# KeyboardInstrument.net
KiCad netlist of a schematic drawn in EAGLE
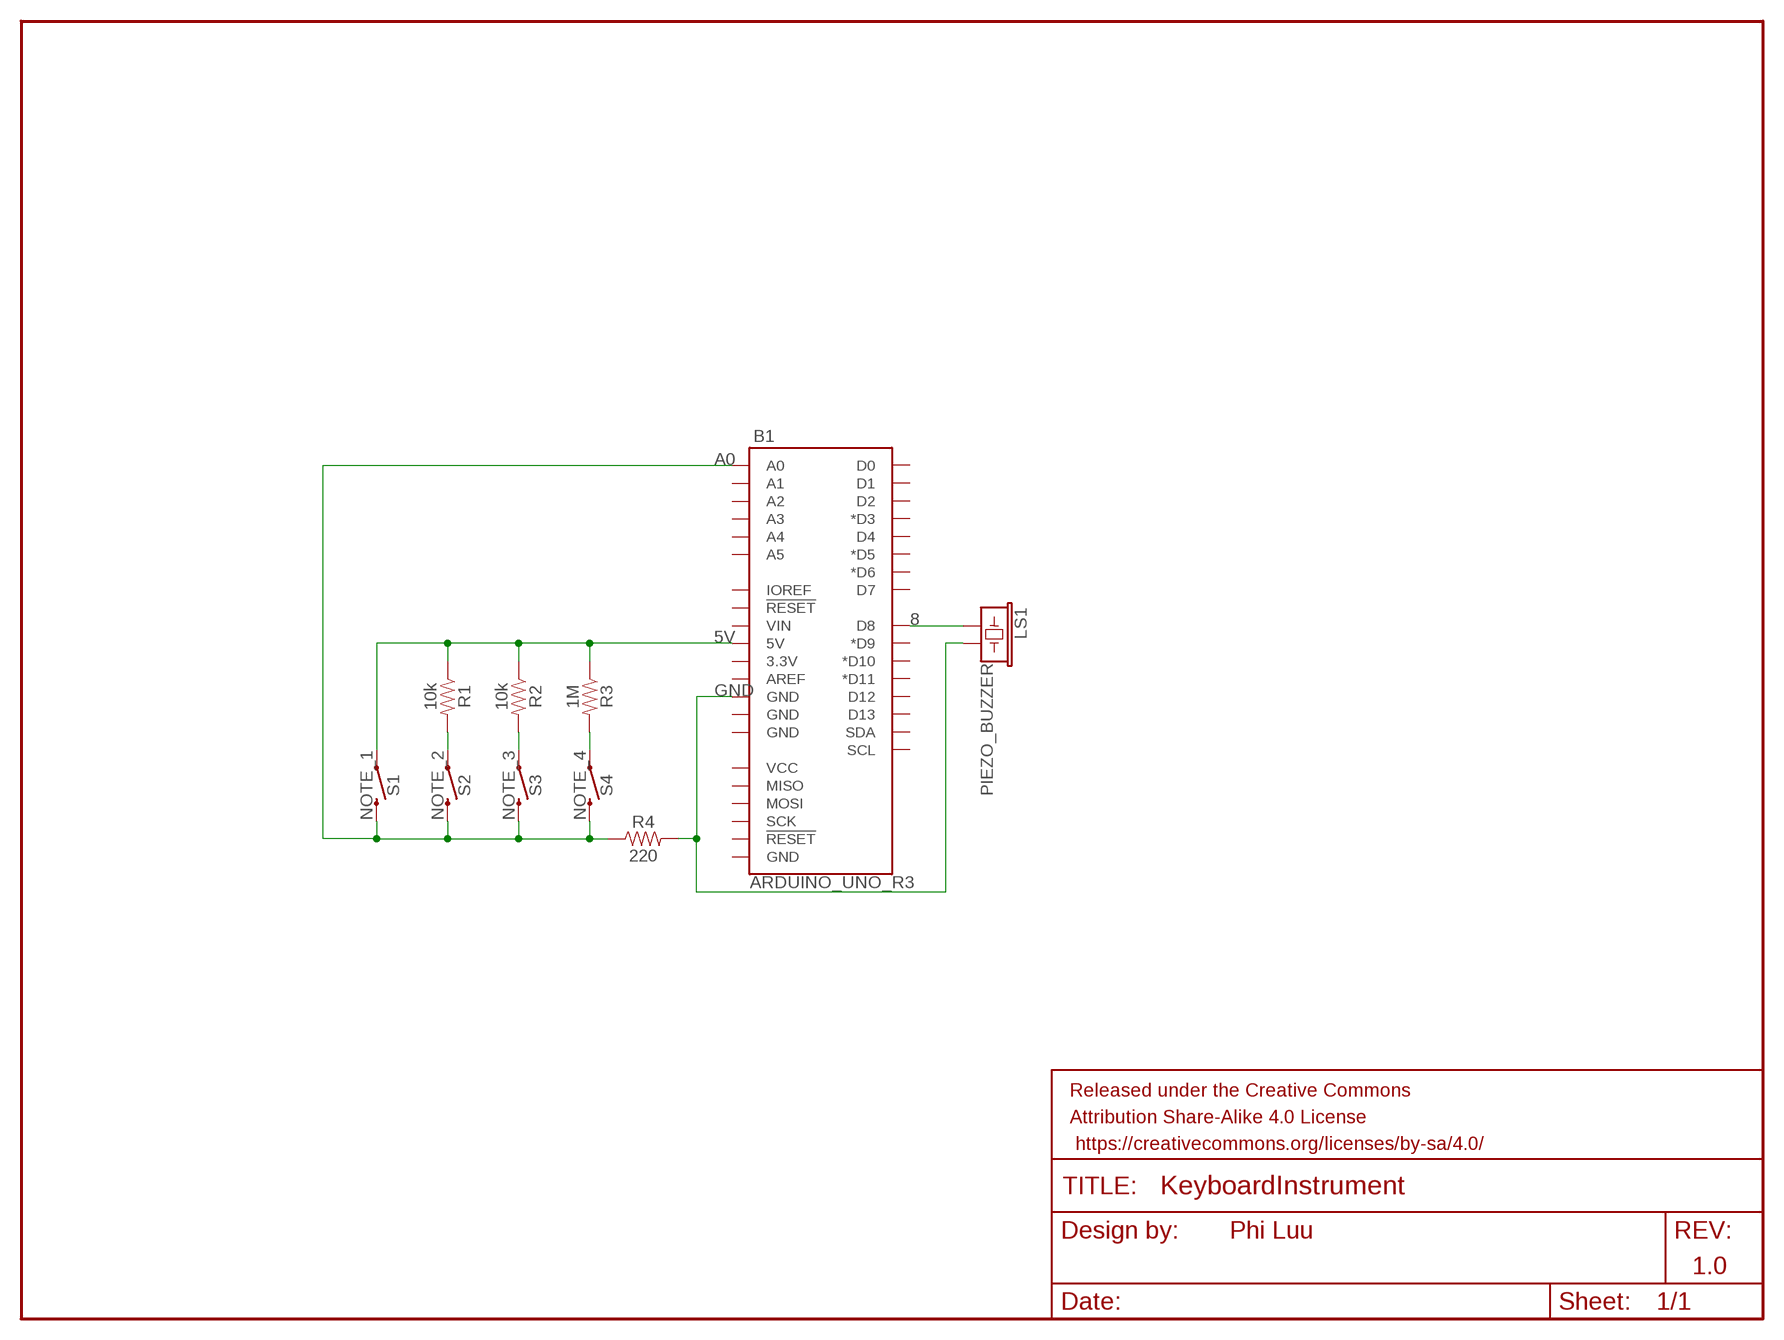
[diagram p0: schematic, sheet 1]

(export (version "E")
  (design (tool "Eeschema 10.0.6"))
  (components
    (comp (ref "B1")
      (value "ARDUINO_UNO_R3")
      (footprint "eagle-import:ARDUINO_R3")
      (libsource (lib "eagle-import") (part "ARDUINO_UNO_R3"))
    )
    (comp (ref "FRAME1")
      (value "FRAME-LETTER")
      (footprint "eagle-import:CREATIVE_COMMONS")
      (libsource (lib "eagle-import") (part "FRAME-LETTER"))
    )
    (comp (ref "LS1")
      (value "PIEZO_BUZZER")
      (footprint "eagle-import:BUZZER-12MM")
      (libsource (lib "eagle-import") (part "BUZZER-PTH"))
    )
    (comp (ref "R1")
      (value "10k")
      (footprint "eagle-import:AXIAL-0.3")
      (libsource (lib "eagle-import") (part "10KOHM-HORIZ-1/4W-5%"))
    )
    (comp (ref "R2")
      (value "10k")
      (footprint "eagle-import:AXIAL-0.3")
      (libsource (lib "eagle-import") (part "10KOHM-HORIZ-1/4W-5%"))
    )
    (comp (ref "R3")
      (value "1M")
      (footprint "eagle-import:AXIAL-0.3")
      (libsource (lib "eagle-import") (part "1MOHM-HORIZ-1/4W-5%"))
    )
    (comp (ref "R4")
      (value "220")
      (footprint "eagle-import:AXIAL-0.3")
      (libsource (lib "eagle-import") (part "1MOHM-HORIZ-1/4W-5%"))
    )
    (comp (ref "S1")
      (value "NOTE_1")
      (footprint "eagle-import:TACTILE_SWITCH_PTH_6.0MM")
      (libsource (lib "eagle-import") (part "MOMENTARY-SWITCH-SPST-PTH-6.0MM"))
    )
    (comp (ref "S2")
      (value "NOTE_2")
      (footprint "eagle-import:TACTILE_SWITCH_PTH_6.0MM")
      (libsource (lib "eagle-import") (part "MOMENTARY-SWITCH-SPST-PTH-6.0MM"))
    )
    (comp (ref "S3")
      (value "NOTE_3")
      (footprint "eagle-import:TACTILE_SWITCH_PTH_6.0MM")
      (libsource (lib "eagle-import") (part "MOMENTARY-SWITCH-SPST-PTH-6.0MM"))
    )
    (comp (ref "S4")
      (value "NOTE_4")
      (footprint "eagle-import:TACTILE_SWITCH_PTH_6.0MM")
      (libsource (lib "eagle-import") (part "MOMENTARY-SWITCH-SPST-PTH-6.0MM"))
    )
  )
  (nets
    (net (code "1") (name "/5V") (class "Default")
      (node (ref "B1") (pin "5V") (pinfunction "5V_5V") (pintype "bidirectional"))
      (node (ref "R1") (pin "P$1") (pinfunction "1_P$1") (pintype "passive"))
      (node (ref "R2") (pin "P$1") (pinfunction "1_P$1") (pintype "passive"))
      (node (ref "R3") (pin "P$1") (pinfunction "1_P$1") (pintype "passive"))
      (node (ref "S1") (pin "1") (pinfunction "1_1") (pintype "passive"))
    )
    (net (code "2") (name "/8") (class "Default")
      (node (ref "B1") (pin "D8") (pinfunction "D8_D8") (pintype "bidirectional"))
      (node (ref "LS1") (pin "+") (pinfunction "1_+") (pintype "passive"))
    )
    (net (code "3") (name "/A0") (class "Default")
      (node (ref "B1") (pin "A0") (pinfunction "A0_A0") (pintype "bidirectional"))
      (node (ref "R4") (pin "P$1") (pinfunction "1_P$1") (pintype "passive"))
      (node (ref "S1") (pin "3") (pinfunction "2_3") (pintype "passive"))
      (node (ref "S2") (pin "3") (pinfunction "2_3") (pintype "passive"))
      (node (ref "S3") (pin "3") (pinfunction "2_3") (pintype "passive"))
      (node (ref "S4") (pin "3") (pinfunction "2_3") (pintype "passive"))
    )
    (net (code "4") (name "/GND") (class "Default")
      (node (ref "B1") (pin "GND@4") (pinfunction "GND_GND@4") (pintype "bidirectional"))
      (node (ref "LS1") (pin "-") (pinfunction "2_-") (pintype "passive"))
      (node (ref "R4") (pin "P$2") (pinfunction "2_P$2") (pintype "passive"))
    )
    (net (code "5") (name "Net-(R1-2)") (class "Default")
      (node (ref "R1") (pin "P$2") (pinfunction "2_P$2") (pintype "passive"))
      (node (ref "S2") (pin "1") (pinfunction "1_1") (pintype "passive"))
    )
    (net (code "6") (name "Net-(R2-2)") (class "Default")
      (node (ref "R2") (pin "P$2") (pinfunction "2_P$2") (pintype "passive"))
      (node (ref "S3") (pin "1") (pinfunction "1_1") (pintype "passive"))
    )
    (net (code "7") (name "Net-(R3-2)") (class "Default")
      (node (ref "R3") (pin "P$2") (pinfunction "2_P$2") (pintype "passive"))
      (node (ref "S4") (pin "1") (pinfunction "1_1") (pintype "passive"))
    )
    (net (code "8") (name "unconnected-(B1-*D3-PadD3)") (class "Default")
      (node (ref "B1") (pin "D3") (pinfunction "*D3_D3") (pintype "bidirectional"))
    )
    (net (code "9") (name "unconnected-(B1-*D5-PadD5)") (class "Default")
      (node (ref "B1") (pin "D5") (pinfunction "*D5_D5") (pintype "bidirectional"))
    )
    (net (code "10") (name "unconnected-(B1-*D6-PadD6)") (class "Default")
      (node (ref "B1") (pin "D6") (pinfunction "*D6_D6") (pintype "bidirectional"))
    )
    (net (code "11") (name "unconnected-(B1-*D9-PadD9)") (class "Default")
      (node (ref "B1") (pin "D9") (pinfunction "*D9_D9") (pintype "bidirectional"))
    )
    (net (code "12") (name "unconnected-(B1-*D10-PadD10)") (class "Default")
      (node (ref "B1") (pin "D10") (pinfunction "*D10_D10") (pintype "bidirectional"))
    )
    (net (code "13") (name "unconnected-(B1-*D11-PadD11)") (class "Default")
      (node (ref "B1") (pin "D11") (pinfunction "*D11_D11") (pintype "bidirectional"))
    )
    (net (code "14") (name "unconnected-(B1-GND-PadGND@1)") (class "Default")
      (node (ref "B1") (pin "GND@1") (pinfunction "GND_GND@1") (pintype "bidirectional"))
    )
    (net (code "15") (name "unconnected-(B1-GND-PadGND@2)") (class "Default")
      (node (ref "B1") (pin "GND@2") (pinfunction "GND_GND@2") (pintype "bidirectional"))
    )
    (net (code "16") (name "unconnected-(B1-GND-PadGND@3)") (class "Default")
      (node (ref "B1") (pin "GND@3") (pinfunction "GND_GND@3") (pintype "bidirectional"))
    )
    (net (code "17") (name "unconnected-(B1-Pad3.3V)") (class "Default")
      (node (ref "B1") (pin "3.3V") (pinfunction "3.3V_3.3V") (pintype "bidirectional"))
    )
    (net (code "18") (name "unconnected-(B1-PadA1)") (class "Default")
      (node (ref "B1") (pin "A1") (pinfunction "A1_A1") (pintype "bidirectional"))
    )
    (net (code "19") (name "unconnected-(B1-PadA2)") (class "Default")
      (node (ref "B1") (pin "A2") (pinfunction "A2_A2") (pintype "bidirectional"))
    )
    (net (code "20") (name "unconnected-(B1-PadA3)") (class "Default")
      (node (ref "B1") (pin "A3") (pinfunction "A3_A3") (pintype "bidirectional"))
    )
    (net (code "21") (name "unconnected-(B1-PadA4)") (class "Default")
      (node (ref "B1") (pin "A4") (pinfunction "A4_A4") (pintype "bidirectional"))
    )
    (net (code "22") (name "unconnected-(B1-PadA5)") (class "Default")
      (node (ref "B1") (pin "A5") (pinfunction "A5_A5") (pintype "bidirectional"))
    )
    (net (code "23") (name "unconnected-(B1-PadAREF)") (class "Default")
      (node (ref "B1") (pin "AREF") (pinfunction "AREF_AREF") (pintype "bidirectional"))
    )
    (net (code "24") (name "unconnected-(B1-PadD0)") (class "Default")
      (node (ref "B1") (pin "D0") (pinfunction "D0_D0") (pintype "bidirectional"))
    )
    (net (code "25") (name "unconnected-(B1-PadD1)") (class "Default")
      (node (ref "B1") (pin "D1") (pinfunction "D1_D1") (pintype "bidirectional"))
    )
    (net (code "26") (name "unconnected-(B1-PadD2)") (class "Default")
      (node (ref "B1") (pin "D2") (pinfunction "D2_D2") (pintype "bidirectional"))
    )
    (net (code "27") (name "unconnected-(B1-PadD4)") (class "Default")
      (node (ref "B1") (pin "D4") (pinfunction "D4_D4") (pintype "bidirectional"))
    )
    (net (code "28") (name "unconnected-(B1-PadD7)") (class "Default")
      (node (ref "B1") (pin "D7") (pinfunction "D7_D7") (pintype "bidirectional"))
    )
    (net (code "29") (name "unconnected-(B1-PadD12)") (class "Default")
      (node (ref "B1") (pin "D12") (pinfunction "D12_D12") (pintype "bidirectional"))
    )
    (net (code "30") (name "unconnected-(B1-PadD13)") (class "Default")
      (node (ref "B1") (pin "D13") (pinfunction "D13_D13") (pintype "bidirectional"))
    )
    (net (code "31") (name "unconnected-(B1-PadIOREF)") (class "Default")
      (node (ref "B1") (pin "IOREF") (pinfunction "IOREF_IOREF") (pintype "bidirectional"))
    )
    (net (code "32") (name "unconnected-(B1-PadMISO)") (class "Default")
      (node (ref "B1") (pin "MISO") (pinfunction "MISO_MISO") (pintype "bidirectional"))
    )
    (net (code "33") (name "unconnected-(B1-PadMOSI)") (class "Default")
      (node (ref "B1") (pin "MOSI") (pinfunction "MOSI_MOSI") (pintype "bidirectional"))
    )
    (net (code "34") (name "unconnected-(B1-PadSCK)") (class "Default")
      (node (ref "B1") (pin "SCK") (pinfunction "SCK_SCK") (pintype "bidirectional"))
    )
    (net (code "35") (name "unconnected-(B1-PadSCL)") (class "Default")
      (node (ref "B1") (pin "SCL") (pinfunction "SCL_SCL") (pintype "bidirectional"))
    )
    (net (code "36") (name "unconnected-(B1-PadSDA)") (class "Default")
      (node (ref "B1") (pin "SDA") (pinfunction "SDA_SDA") (pintype "bidirectional"))
    )
    (net (code "37") (name "unconnected-(B1-PadVCC)") (class "Default")
      (node (ref "B1") (pin "VCC") (pinfunction "VCC_VCC") (pintype "bidirectional"))
    )
    (net (code "38") (name "unconnected-(B1-PadVIN)") (class "Default")
      (node (ref "B1") (pin "VIN") (pinfunction "VIN_VIN") (pintype "bidirectional"))
    )
    (net (code "39") (name "unconnected-(B1-~{RESET}-PadRESET@1)") (class "Default")
      (node (ref "B1") (pin "RESET@1") (pinfunction "~{RESET}_RESET@1") (pintype "bidirectional"))
    )
    (net (code "40") (name "unconnected-(B1-~{RESET}-PadRESET@2)") (class "Default")
      (node (ref "B1") (pin "RESET@2") (pinfunction "~{RESET}_RESET@2") (pintype "bidirectional"))
    )
  )
)
